# DC-DC_Protection.net
KiCad netlist of a schematic drawn in Altium Designer
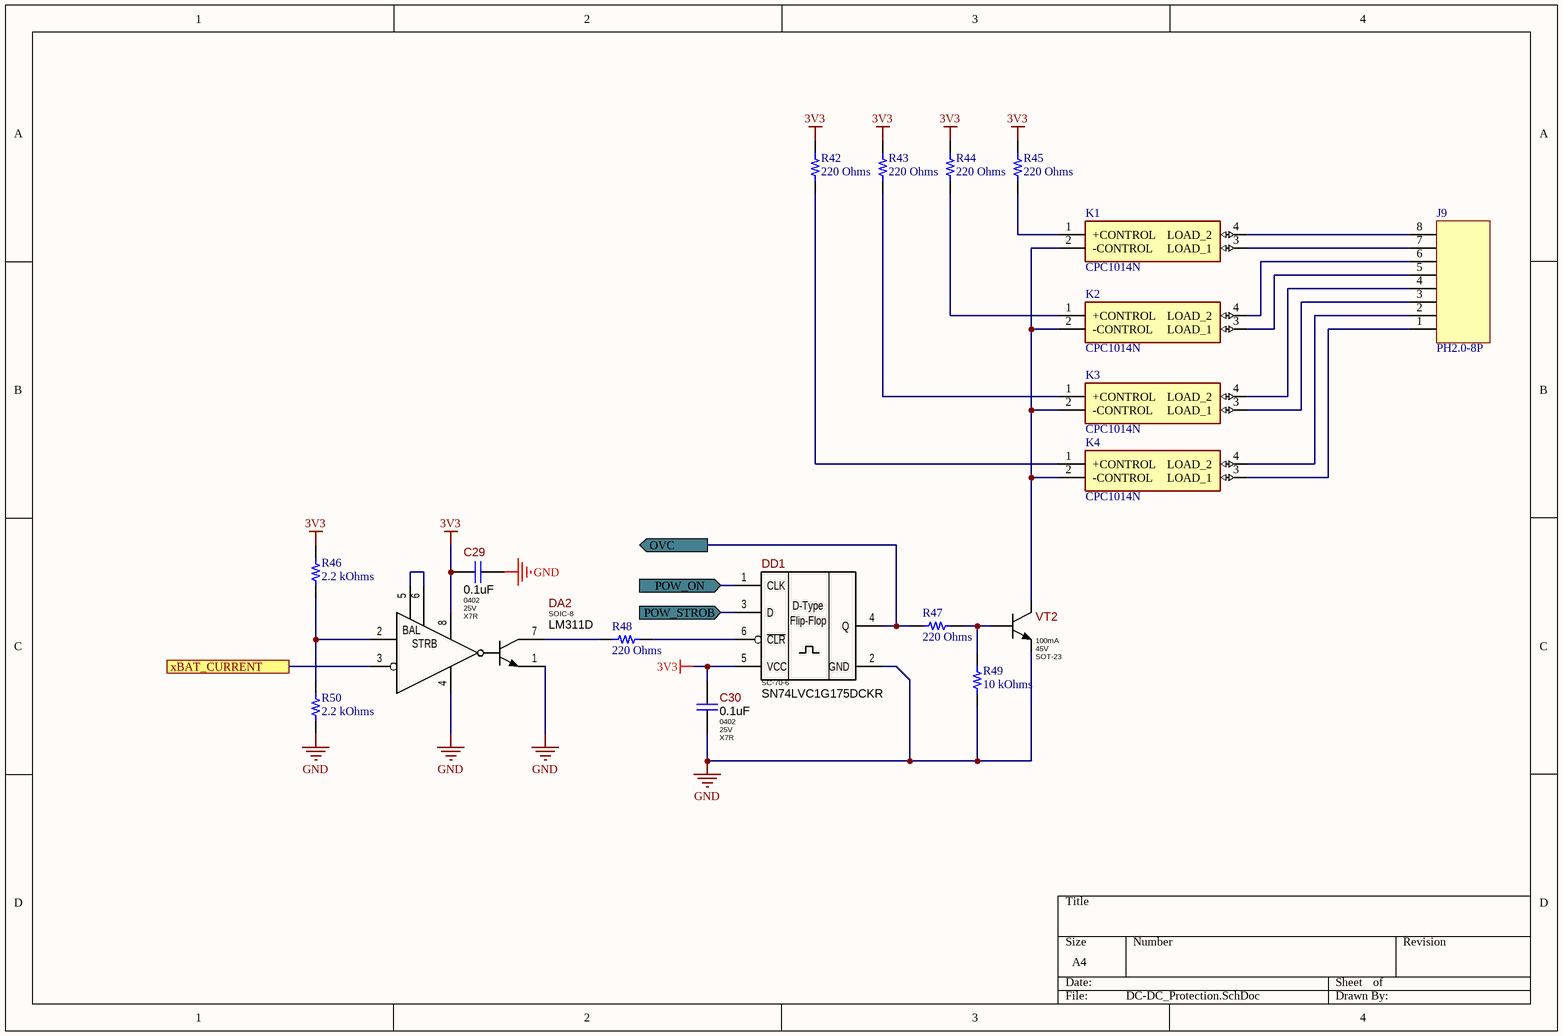
[diagram p0: DC-DC_Protection.SchDoc]

(export (version "E")
  (design (tool "Eeschema 10.0.6"))
  (components
    (comp (ref "C29")
      (value "0.1uF")
      (footprint "C_CERAMIC_0402_MED")
      (description "100nF 25V X7R ±10% 0402 Ceramic Capacitor RoHS")
      (fields
        (field (name "PACKAGE") "0402")
        (field (name "VOLTAGE") "25V")
        (field (name "DIELECTRIC TYPE") "X7R")
        (field (name "PART NUMBER") "GRM155R71E104KE14D")
        (field (name "MANUFACTURER") "Murata Electronics")
      )
      (libsource (lib "AjaxLibrary") (part "Capacitor-NonPolar"))
    )
    (comp (ref "C30")
      (value "0.1uF")
      (footprint "C_CERAMIC_0402_MED")
      (description "100nF 25V X7R ±10% 0402 Ceramic Capacitor RoHS")
      (fields
        (field (name "PACKAGE") "0402")
        (field (name "VOLTAGE") "25V")
        (field (name "DIELECTRIC TYPE") "X7R")
        (field (name "PART NUMBER") "GRM155R71E104KE14D")
        (field (name "MANUFACTURER") "Murata Electronics")
      )
      (libsource (lib "AjaxLibrary") (part "Capacitor-NonPolar"))
    )
    (comp (ref "DA2")
      (value "LM311D")
      (footprint "SOIC-8_W3.9MM")
      (description "Differential General Purpose Comparator with Open-Collector, Open-Emitter, SOIC-8")
      (fields
        (field (name "PACKAGE") "SOIC-8")
        (field (name "PART NUMBER") "LM311D")
        (field (name "MANUFACTURER") "Texas Instruments")
      )
      (libsource (lib "IC") (part "LM311D"))
    )
    (comp (ref "DD1")
      (value "SN74LVC1G175DCKR")
      (footprint "SC-70-6")
      (description "Single D-type Flip-Flop with Asynchronous Clear, Positive Edge Trigger, SC-70-6")
      (fields
        (field (name "PACKAGE") "SC-70-6")
        (field (name "PART NUMBER") "SN74LVC1G175DCKR")
        (field (name "MANUFACTURER") "Texas Instruments")
      )
      (libsource (lib "AjaxLibrary") (part "SN74LVC1G175DCKR"))
    )
    (comp (ref "J9") (value "PH2.0-8P") (footprint "PH2.0-8P") (libsource (lib "PH") (part "PH2.0-8P")))
    (comp (ref "K1")
      (value "CPC1014N")
      (footprint "SamacSys:SOP254P610X218-4N")
      (description "Relay or Contactor")
      (fields (field (name "MOUSER PART NUMBER") "849-CPC1014N"))
      (libsource (lib "*") (part "CPC1014N"))
    )
    (comp (ref "K2")
      (value "CPC1014N")
      (footprint "SamacSys:SOP254P610X218-4N")
      (description "Relay or Contactor")
      (fields (field (name "MOUSER PART NUMBER") "849-CPC1014N"))
      (libsource (lib "*") (part "CPC1014N"))
    )
    (comp (ref "K3")
      (value "CPC1014N")
      (footprint "SamacSys:SOP254P610X218-4N")
      (description "Relay or Contactor")
      (fields (field (name "MOUSER PART NUMBER") "849-CPC1014N"))
      (libsource (lib "*") (part "CPC1014N"))
    )
    (comp (ref "K4")
      (value "CPC1014N")
      (footprint "SamacSys:SOP254P610X218-4N")
      (description "Relay or Contactor")
      (fields (field (name "MOUSER PART NUMBER") "849-CPC1014N"))
      (libsource (lib "*") (part "CPC1014N"))
    )
    (comp (ref "R42")
      (value "220 Ohms")
      (footprint "RES 0805_2012")
      (description "RES SMD 220 OHM 1% 0.4W 0805")
      (fields (field (name "PART NUMBER") "ESR10EZPF2200") (field (name "MANUFACTURER") "Rohm Semiconductor"))
      (libsource (lib "Celestial Altium Library - altium_library") (part "Resistor"))
    )
    (comp (ref "R43")
      (value "220 Ohms")
      (footprint "RES 0805_2012")
      (description "RES SMD 220 OHM 1% 0.4W 0805")
      (fields (field (name "PART NUMBER") "ESR10EZPF2200") (field (name "MANUFACTURER") "Rohm Semiconductor"))
      (libsource (lib "Celestial Altium Library - altium_library") (part "Resistor"))
    )
    (comp (ref "R44")
      (value "220 Ohms")
      (footprint "RES 0805_2012")
      (description "RES SMD 220 OHM 1% 0.4W 0805")
      (fields (field (name "PART NUMBER") "ESR10EZPF2200") (field (name "MANUFACTURER") "Rohm Semiconductor"))
      (libsource (lib "Celestial Altium Library - altium_library") (part "Resistor"))
    )
    (comp (ref "R45")
      (value "220 Ohms")
      (footprint "RES 0805_2012")
      (description "RES SMD 220 OHM 1% 0.4W 0805")
      (fields (field (name "PART NUMBER") "ESR10EZPF2200") (field (name "MANUFACTURER") "Rohm Semiconductor"))
      (libsource (lib "Celestial Altium Library - altium_library") (part "Resistor"))
    )
    (comp (ref "R46")
      (value "2.2 kOhms")
      (footprint "RES 0805_2012")
      (description "RES SMD 2.2K OHM 5% 1/4W 0805")
      (fields (field (name "PART NUMBER") "SR0805JR-7W2K2L") (field (name "MANUFACTURER") "Yageo"))
      (libsource (lib "Celestial Altium Library - altium_library") (part "Resistor"))
    )
    (comp (ref "R47")
      (value "220 Ohms")
      (footprint "RES 0805_2012")
      (description "RES SMD 220 OHM 1% 0.4W 0805")
      (fields (field (name "PART NUMBER") "ESR10EZPF2200") (field (name "MANUFACTURER") "Rohm Semiconductor"))
      (libsource (lib "Celestial Altium Library - altium_library") (part "Resistor"))
    )
    (comp (ref "R48")
      (value "220 Ohms")
      (footprint "RES 0805_2012")
      (description "CRGP 0805 220R 1%")
      (fields
        (field (name "PART NUMBER") "CRGP0805F220R")
        (field (name "MANUFACTURER") "TE Connectivity Passive Product")
      )
      (libsource (lib "Celestial Altium Library - altium_library") (part "Resistor"))
    )
    (comp (ref "R49")
      (value "10 kOhms")
      (footprint "RES 0805_2012")
      (description "RES 10K OHM 0.1% 1/10W 0805")
      (fields
        (field (name "PART NUMBER") "RNCS0805BKE10K0")
        (field (name "MANUFACTURER") "Stackpole Electronics Inc")
      )
      (libsource (lib "Celestial Altium Library - altium_library") (part "Resistor"))
    )
    (comp (ref "R50")
      (value "2.2 kOhms")
      (footprint "RES 0805_2012")
      (description "RES SMD 2.2K OHM 5% 1/4W 0805")
      (fields (field (name "PART NUMBER") "SR0805JR-7W2K2L") (field (name "MANUFACTURER") "Yageo"))
      (libsource (lib "Celestial Altium Library - altium_library") (part "Resistor"))
    )
    (comp (ref "VT2")
      (value "BC847B")
      (footprint "SOT-23_MED")
      (description "45V, 100mA NPN General Purpose Transistor")
      (fields
        (field (name "IC") "100mA")
        (field (name "VCE") "45V")
        (field (name "PACKAGE") "SOT-23")
        (field (name "MANUFACTURER") "Nexperia USA Inc.")
      )
      (libsource (lib "AjaxLibrary") (part "Bipolar-NPN"))
    )
  )
  (nets
    (net (code "1") (name "/OVC") (class "Default")
      (node (ref "DD1") (pin "4") (pinfunction "Q_4") (pintype "passive"))
      (node (ref "R47") (pin "1") (pinfunction "1_1") (pintype "passive"))
    )
    (net (code "2") (name "/POW_ON") (class "Default")
      (node (ref "DD1") (pin "1") (pinfunction "CLK_1") (pintype "passive"))
    )
    (net (code "3") (name "/POW_STROB") (class "Default")
      (node (ref "DD1") (pin "3") (pinfunction "D_3") (pintype "passive"))
    )
    (net (code "4") (name "/xBAT_CURRENT") (class "Default")
      (node (ref "DA2") (pin "3") (pinfunction "IN-_3") (pintype "passive"))
    )
    (net (code "5") (name "3V3") (class "Default")
      (node (ref "C29") (pin "1") (pinfunction "1_1") (pintype "passive"))
      (node (ref "C30") (pin "1") (pinfunction "1_1") (pintype "passive"))
      (node (ref "DA2") (pin "8") (pinfunction "VCC_8") (pintype "passive"))
      (node (ref "DD1") (pin "5") (pinfunction "VCC_5") (pintype "passive"))
      (node (ref "R42") (pin "2") (pinfunction "2_2") (pintype "passive"))
      (node (ref "R43") (pin "2") (pinfunction "2_2") (pintype "passive"))
      (node (ref "R44") (pin "2") (pinfunction "2_2") (pintype "passive"))
      (node (ref "R45") (pin "2") (pinfunction "2_2") (pintype "passive"))
      (node (ref "R46") (pin "2") (pinfunction "2_2") (pintype "passive"))
    )
    (net (code "6") (name "GND") (class "Default")
      (node (ref "C29") (pin "2") (pinfunction "2_2") (pintype "passive"))
      (node (ref "C30") (pin "2") (pinfunction "2_2") (pintype "passive"))
      (node (ref "DA2") (pin "1") (pinfunction "EMIT_OUT_1") (pintype "passive"))
      (node (ref "DA2") (pin "4") (pinfunction "GND_4") (pintype "passive"))
      (node (ref "DD1") (pin "2") (pinfunction "GND_2") (pintype "passive"))
      (node (ref "R49") (pin "1") (pinfunction "1_1") (pintype "passive"))
      (node (ref "R50") (pin "1") (pinfunction "1_1") (pintype "passive"))
      (node (ref "VT2") (pin "2") (pinfunction "E_2") (pintype "passive"))
    )
    (net (code "7") (name "Net-(DA2-BALANCE)") (class "Default")
      (node (ref "DA2") (pin "5") (pinfunction "BALANCE_5") (pintype "passive"))
      (node (ref "DA2") (pin "6") (pinfunction "BAL/STRB_6") (pintype "passive"))
    )
    (net (code "8") (name "Net-(DA2-COL_OUT)") (class "Default")
      (node (ref "DA2") (pin "7") (pinfunction "COL_OUT_7") (pintype "passive"))
      (node (ref "R48") (pin "1") (pinfunction "1_1") (pintype "passive"))
    )
    (net (code "9") (name "Net-(DA2-IN+)") (class "Default")
      (node (ref "DA2") (pin "2") (pinfunction "IN+_2") (pintype "passive"))
      (node (ref "R46") (pin "1") (pinfunction "1_1") (pintype "passive"))
      (node (ref "R50") (pin "2") (pinfunction "2_2") (pintype "passive"))
    )
    (net (code "10") (name "Net-(DD1-~{CLR})") (class "Default")
      (node (ref "DD1") (pin "6") (pinfunction "~{CLR}_6") (pintype "passive"))
      (node (ref "R48") (pin "2") (pinfunction "2_2") (pintype "passive"))
    )
    (net (code "11") (name "Net-(K1-+CONTROL)") (class "Default")
      (node (ref "K1") (pin "1") (pinfunction "+CONTROL_1") (pintype "power_in"))
      (node (ref "R45") (pin "1") (pinfunction "1_1") (pintype "passive"))
    )
    (net (code "12") (name "Net-(K1--CONTROL)") (class "Default")
      (node (ref "K1") (pin "2") (pinfunction "-CONTROL_2") (pintype "power_in"))
      (node (ref "K2") (pin "2") (pinfunction "-CONTROL_2") (pintype "power_in"))
      (node (ref "K3") (pin "2") (pinfunction "-CONTROL_2") (pintype "power_in"))
      (node (ref "K4") (pin "2") (pinfunction "-CONTROL_2") (pintype "power_in"))
      (node (ref "VT2") (pin "3") (pinfunction "C_3") (pintype "passive"))
    )
    (net (code "13") (name "Net-(K1-LOAD_1)") (class "Default")
      (node (ref "J9") (pin "7") (pinfunction "7_7") (pintype "passive"))
      (node (ref "K1") (pin "3") (pinfunction "LOAD_1_3") (pintype "bidirectional"))
    )
    (net (code "14") (name "Net-(K1-LOAD_2)") (class "Default")
      (node (ref "J9") (pin "8") (pinfunction "8_8") (pintype "passive"))
      (node (ref "K1") (pin "4") (pinfunction "LOAD_2_4") (pintype "bidirectional"))
    )
    (net (code "15") (name "Net-(K2-+CONTROL)") (class "Default")
      (node (ref "K2") (pin "1") (pinfunction "+CONTROL_1") (pintype "power_in"))
      (node (ref "R44") (pin "1") (pinfunction "1_1") (pintype "passive"))
    )
    (net (code "16") (name "Net-(K2-LOAD_1)") (class "Default")
      (node (ref "J9") (pin "5") (pinfunction "5_5") (pintype "passive"))
      (node (ref "K2") (pin "3") (pinfunction "LOAD_1_3") (pintype "bidirectional"))
    )
    (net (code "17") (name "Net-(K2-LOAD_2)") (class "Default")
      (node (ref "J9") (pin "6") (pinfunction "6_6") (pintype "passive"))
      (node (ref "K2") (pin "4") (pinfunction "LOAD_2_4") (pintype "bidirectional"))
    )
    (net (code "18") (name "Net-(K3-+CONTROL)") (class "Default")
      (node (ref "K3") (pin "1") (pinfunction "+CONTROL_1") (pintype "power_in"))
      (node (ref "R43") (pin "1") (pinfunction "1_1") (pintype "passive"))
    )
    (net (code "19") (name "Net-(K3-LOAD_1)") (class "Default")
      (node (ref "J9") (pin "3") (pinfunction "3_3") (pintype "passive"))
      (node (ref "K3") (pin "3") (pinfunction "LOAD_1_3") (pintype "bidirectional"))
    )
    (net (code "20") (name "Net-(K3-LOAD_2)") (class "Default")
      (node (ref "J9") (pin "4") (pinfunction "4_4") (pintype "passive"))
      (node (ref "K3") (pin "4") (pinfunction "LOAD_2_4") (pintype "bidirectional"))
    )
    (net (code "21") (name "Net-(K4-+CONTROL)") (class "Default")
      (node (ref "K4") (pin "1") (pinfunction "+CONTROL_1") (pintype "power_in"))
      (node (ref "R42") (pin "1") (pinfunction "1_1") (pintype "passive"))
    )
    (net (code "22") (name "Net-(K4-LOAD_1)") (class "Default")
      (node (ref "J9") (pin "1") (pinfunction "1_1") (pintype "passive"))
      (node (ref "K4") (pin "3") (pinfunction "LOAD_1_3") (pintype "bidirectional"))
    )
    (net (code "23") (name "Net-(K4-LOAD_2)") (class "Default")
      (node (ref "J9") (pin "2") (pinfunction "2_2") (pintype "passive"))
      (node (ref "K4") (pin "4") (pinfunction "LOAD_2_4") (pintype "bidirectional"))
    )
    (net (code "24") (name "Net-(VT2-B)") (class "Default")
      (node (ref "R47") (pin "2") (pinfunction "2_2") (pintype "passive"))
      (node (ref "R49") (pin "2") (pinfunction "2_2") (pintype "passive"))
      (node (ref "VT2") (pin "1") (pinfunction "B_1") (pintype "passive"))
    )
  )
)
